# ReSpeaker_HPF_V01.net
KiCad netlist of a schematic drawn in EAGLE
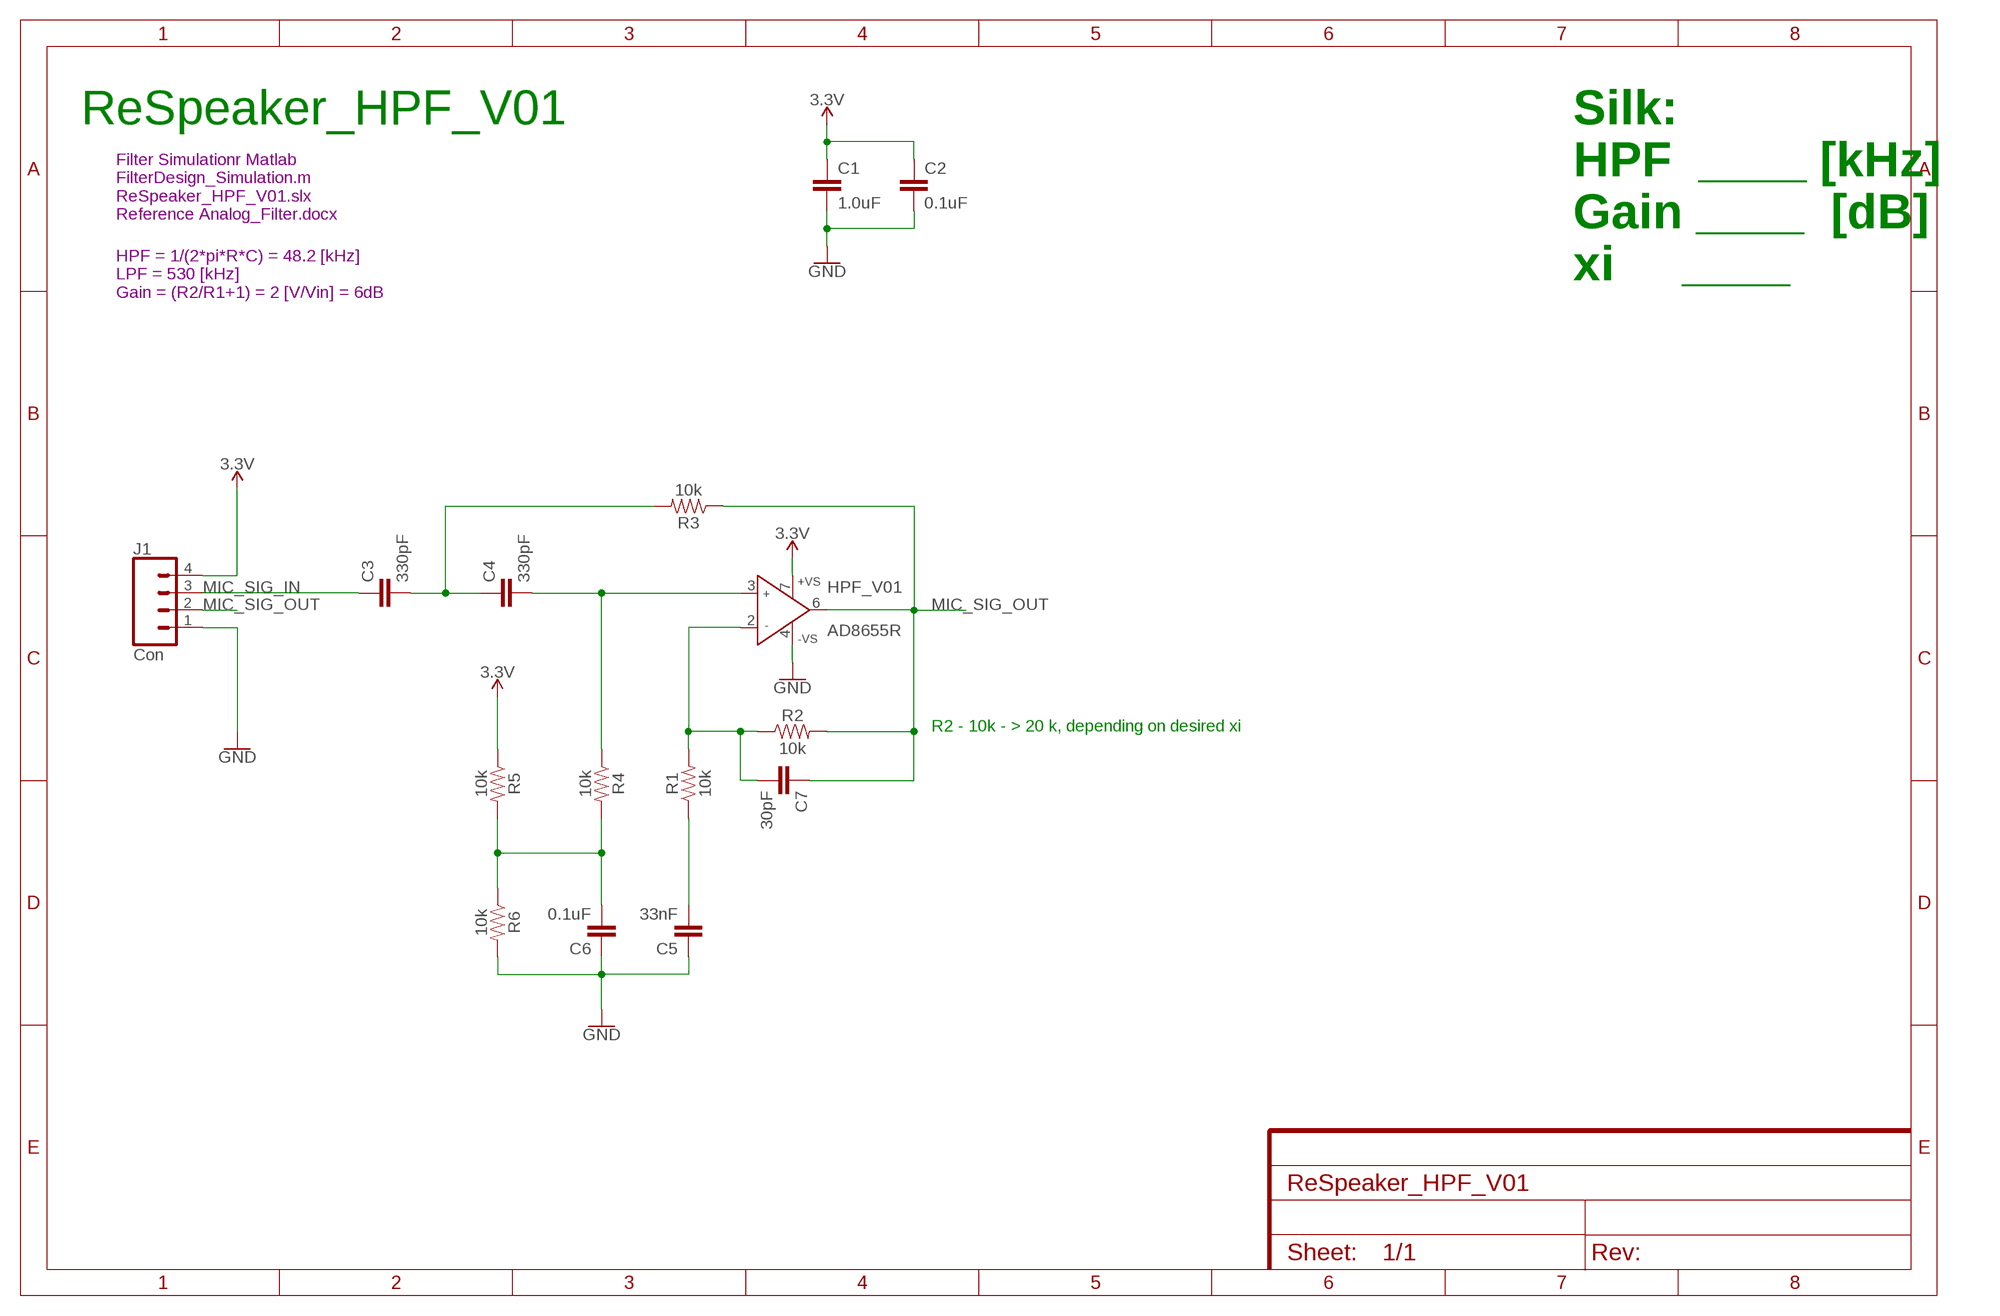
[diagram p0: schematic, sheet 1]

(export (version "E")
  (design (tool "Eeschema 10.0.6"))
  (components
    (comp (ref "C1")
      (value "1.0uF")
      (footprint "eagle-import:0805")
      (libsource (lib "eagle-import") (part "1.0UF-0805-25V-10%"))
    )
    (comp (ref "C2")
      (value "0.1uF")
      (footprint "eagle-import:0805")
      (libsource (lib "eagle-import") (part "1.0UF-0805-25V-10%"))
    )
    (comp (ref "C3")
      (value "330pF")
      (footprint "eagle-import:0805")
      (libsource (lib "eagle-import") (part "1.0UF-0805-25V-10%"))
    )
    (comp (ref "C4")
      (value "330pF")
      (footprint "eagle-import:0805")
      (libsource (lib "eagle-import") (part "1.0UF-0805-25V-10%"))
    )
    (comp (ref "C5")
      (value "33nF")
      (footprint "eagle-import:0805")
      (libsource (lib "eagle-import") (part "1.0UF-0805-25V-10%"))
    )
    (comp (ref "C6")
      (value "0.1uF")
      (footprint "eagle-import:0805")
      (libsource (lib "eagle-import") (part "1.0UF-0805-25V-10%"))
    )
    (comp (ref "C7")
      (value "30pF")
      (footprint "eagle-import:0805")
      (libsource (lib "eagle-import") (part "1.0UF-0805-25V-10%"))
    )
    (comp (ref "HPF_V01")
      (value "AD8655R")
      (footprint "eagle-import:SO8")
      (fields (field (name "MF") "ALTERA CORPORATION") (field (name "MPN") "AD8655ARMZ-REEL"))
      (libsource (lib "eagle-import") (part "AD8655R"))
    )
    (comp (ref "J1")
      (value "Con")
      (footprint "eagle-import:1X04")
      (libsource (lib "eagle-import") (part "CONN_04"))
    )
    (comp (ref "R1")
      (value "10k")
      (footprint "eagle-import:0805")
      (libsource (lib "eagle-import") (part "RESISTOR0805"))
    )
    (comp (ref "R2")
      (value "10k")
      (footprint "eagle-import:0805")
      (libsource (lib "eagle-import") (part "RESISTOR0805"))
    )
    (comp (ref "R3")
      (value "10k")
      (footprint "eagle-import:0805")
      (libsource (lib "eagle-import") (part "RESISTOR0805"))
    )
    (comp (ref "R4")
      (value "10k")
      (footprint "eagle-import:0805")
      (libsource (lib "eagle-import") (part "RESISTOR0805"))
    )
    (comp (ref "R5")
      (value "10k")
      (footprint "eagle-import:0805")
      (libsource (lib "eagle-import") (part "RESISTOR0805"))
    )
    (comp (ref "R6")
      (value "10k")
      (footprint "eagle-import:0805")
      (libsource (lib "eagle-import") (part "RESISTOR0805"))
    )
  )
  (nets
    (net (code "1") (name "/MIC_SIG_IN") (class "Default")
      (node (ref "C3") (pin "1") (pinfunction "1_1") (pintype "passive"))
      (node (ref "J1") (pin "3") (pinfunction "3_3") (pintype "passive"))
    )
    (net (code "2") (name "/MIC_SIG_OUT") (class "Default")
      (node (ref "C7") (pin "1") (pinfunction "1_1") (pintype "passive"))
      (node (ref "HPF_V01") (pin "6") (pinfunction "OUT_6") (pintype "output"))
      (node (ref "J1") (pin "2") (pinfunction "2_2") (pintype "passive"))
      (node (ref "R2") (pin "2") (pinfunction "2_2") (pintype "passive"))
      (node (ref "R3") (pin "1") (pinfunction "1_1") (pintype "passive"))
    )
    (net (code "3") (name "3.3V") (class "Default")
      (node (ref "C1") (pin "1") (pinfunction "1_1") (pintype "passive"))
      (node (ref "C2") (pin "1") (pinfunction "1_1") (pintype "passive"))
      (node (ref "HPF_V01") (pin "7") (pinfunction "+VS_7") (pintype "input"))
      (node (ref "J1") (pin "4") (pinfunction "4_4") (pintype "passive"))
      (node (ref "R5") (pin "1") (pinfunction "1_1") (pintype "passive"))
    )
    (net (code "4") (name "GND") (class "Default")
      (node (ref "C1") (pin "2") (pinfunction "2_2") (pintype "passive"))
      (node (ref "C2") (pin "2") (pinfunction "2_2") (pintype "passive"))
      (node (ref "C5") (pin "1") (pinfunction "1_1") (pintype "passive"))
      (node (ref "C6") (pin "1") (pinfunction "1_1") (pintype "passive"))
      (node (ref "HPF_V01") (pin "4") (pinfunction "-VS_4") (pintype "input"))
      (node (ref "J1") (pin "1") (pinfunction "1_1") (pintype "passive"))
      (node (ref "R6") (pin "2") (pinfunction "2_2") (pintype "passive"))
    )
    (net (code "5") (name "Net-(C3-Pad2)") (class "Default")
      (node (ref "C3") (pin "2") (pinfunction "2_2") (pintype "passive"))
      (node (ref "C4") (pin "1") (pinfunction "1_1") (pintype "passive"))
      (node (ref "R3") (pin "2") (pinfunction "2_2") (pintype "passive"))
    )
    (net (code "6") (name "Net-(C5-Pad2)") (class "Default")
      (node (ref "C5") (pin "2") (pinfunction "2_2") (pintype "passive"))
      (node (ref "R1") (pin "1") (pinfunction "1_1") (pintype "passive"))
    )
    (net (code "7") (name "Net-(C6-Pad2)") (class "Default")
      (node (ref "C6") (pin "2") (pinfunction "2_2") (pintype "passive"))
      (node (ref "R4") (pin "2") (pinfunction "2_2") (pintype "passive"))
      (node (ref "R5") (pin "2") (pinfunction "2_2") (pintype "passive"))
      (node (ref "R6") (pin "1") (pinfunction "1_1") (pintype "passive"))
    )
    (net (code "8") (name "Net-(HPF_V01-IN+)") (class "Default")
      (node (ref "C4") (pin "2") (pinfunction "2_2") (pintype "passive"))
      (node (ref "HPF_V01") (pin "3") (pinfunction "IN+_3") (pintype "input"))
      (node (ref "R4") (pin "1") (pinfunction "1_1") (pintype "passive"))
    )
    (net (code "9") (name "Net-(HPF_V01-IN-)") (class "Default")
      (node (ref "C7") (pin "2") (pinfunction "2_2") (pintype "passive"))
      (node (ref "HPF_V01") (pin "2") (pinfunction "IN-_2") (pintype "input"))
      (node (ref "R1") (pin "2") (pinfunction "2_2") (pintype "passive"))
      (node (ref "R2") (pin "1") (pinfunction "1_1") (pintype "passive"))
    )
  )
)
